# Stylophone.net
KiCad netlist of a schematic drawn in Altium Designer
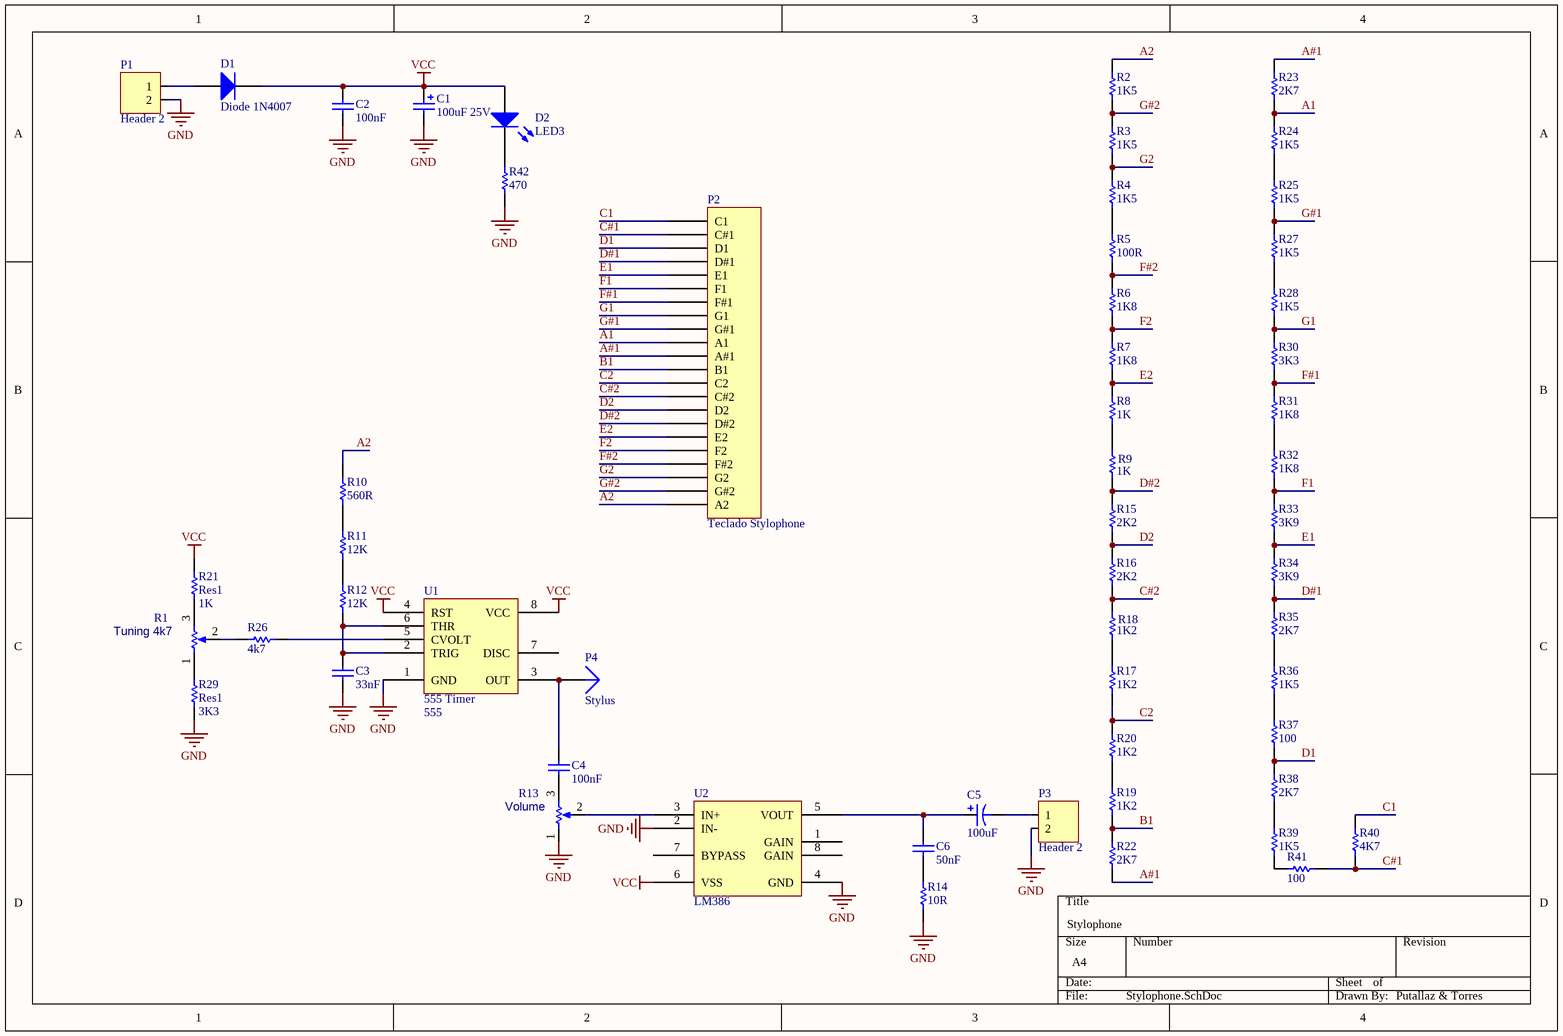
[diagram p0: Stylophone.SchDoc]

(export (version "E")
  (design (tool "Eeschema 10.0.6"))
  (components
    (comp (ref "C1")
      (value "100uF 25V")
      (footprint "CAP SMD 100uF 25V")
      (description "Polarized Capacitor (Radial)")
      (fields (field (name "PUBLISHER") "Altium Limited"))
      (libsource (lib "SchLibPutallaz") (part "Cap Pol1"))
    )
    (comp (ref "C2")
      (value "100nF")
      (footprint "0805 res-cap")
      (description "Capacitor")
      (fields (field (name "PUBLISHER") "Altium Limited"))
      (libsource (lib "SchLibPutallaz") (part "Cap"))
    )
    (comp (ref "C3")
      (value "33nF")
      (footprint "0805 res-cap")
      (description "Capacitor")
      (fields (field (name "PUBLISHER") "Altium Limited"))
      (libsource (lib "SchLibPutallaz") (part "Cap"))
    )
    (comp (ref "C4")
      (value "100nF")
      (footprint "0805 res-cap")
      (description "Capacitor")
      (fields (field (name "PUBLISHER") "Altium Limited"))
      (libsource (lib "SchLibPutallaz") (part "Cap"))
    )
    (comp (ref "C5")
      (value "100uF")
      (footprint "CAP SMD 100uF 25V")
      (description "Polarized Capacitor (Axial)")
      (fields (field (name "PUBLISHER") "Altium Limited"))
      (libsource (lib "SchLibPutallaz") (part "Cap Pol D16mm"))
    )
    (comp (ref "C6")
      (value "50nF")
      (footprint "0805 res-cap")
      (description "Capacitor")
      (fields (field (name "PUBLISHER") "Altium Limited"))
      (libsource (lib "SchLibPutallaz") (part "Cap"))
    )
    (comp (ref "D1")
      (value "Diode 1N4007")
      (footprint "DO214AC")
      (description "1 Amp General Purpose Rectifier")
      (fields (field (name "PUBLISHER") "Altium Limited"))
      (libsource (lib "SchLibPutallaz") (part "Diode 1N4007"))
    )
    (comp (ref "D2")
      (value "LED3")
      (footprint "1206 LED")
      (description "Typical BLUE SiC LED")
      (fields (field (name "PUBLISHER") "Altium Limited"))
      (libsource (lib "SchLibPutallaz") (part "LED3"))
    )
    (comp (ref "P1")
      (value "Header 2")
      (footprint "HDR1X2")
      (description "Header, 2-Pin")
      (fields (field (name "PUBLISHER") "Altium Limited"))
      (libsource (lib "SchLibPutallaz") (part "Header 2"))
    )
    (comp (ref "P2")
      (value "Teclado Stylophone")
      (footprint "Teclado Stylophone")
      (libsource (lib "SchLibPutallaz") (part "Teclado Stylophone"))
    )
    (comp (ref "P3")
      (value "Header 2")
      (footprint "HDR1X2")
      (description "Header, 2-Pin")
      (fields (field (name "PUBLISHER") "Altium Limited"))
      (libsource (lib "") (part "Header 2_1"))
    )
    (comp (ref "P4")
      (value "Stylus")
      (footprint "PIN1")
      (description "Plug")
      (fields (field (name "PUBLISHER") "Altium Limited"))
      (libsource (lib "Miscellaneous Connectors") (part "Plug"))
    )
    (comp (ref "R1")
      (value "Tuning 4k7")
      (footprint "TRIMMING POTENTIOMETER")
      (description "4K7")
      (libsource (lib "Simulation Generic Components") (part "Potentiometer"))
    )
    (comp (ref "R2")
      (value "1K5")
      (footprint "0805 res")
      (description "Resistor")
      (fields (field (name "PUBLISHER") "Altium Limited"))
      (libsource (lib "SchLibPutallaz") (part "Res1"))
    )
    (comp (ref "R3")
      (value "1K5")
      (footprint "0805 res")
      (description "Resistor")
      (fields (field (name "PUBLISHER") "Altium Limited"))
      (libsource (lib "SchLibPutallaz") (part "Res1"))
    )
    (comp (ref "R4")
      (value "1K5")
      (footprint "0805 res")
      (description "Resistor")
      (fields (field (name "PUBLISHER") "Altium Limited"))
      (libsource (lib "SchLibPutallaz") (part "Res1"))
    )
    (comp (ref "R5")
      (value "100R")
      (footprint "0805 res")
      (description "Resistor")
      (fields (field (name "PUBLISHER") "Altium Limited"))
      (libsource (lib "SchLibPutallaz") (part "Res1"))
    )
    (comp (ref "R6")
      (value "1K8")
      (footprint "0805 res")
      (description "Resistor")
      (fields (field (name "PUBLISHER") "Altium Limited"))
      (libsource (lib "SchLibPutallaz") (part "Res1"))
    )
    (comp (ref "R7")
      (value "1K8")
      (footprint "0805 res")
      (description "Resistor")
      (fields (field (name "PUBLISHER") "Altium Limited"))
      (libsource (lib "SchLibPutallaz") (part "Res1"))
    )
    (comp (ref "R8")
      (value "1K")
      (footprint "0805 res")
      (description "Resistor")
      (fields (field (name "PUBLISHER") "Altium Limited"))
      (libsource (lib "SchLibPutallaz") (part "Res1"))
    )
    (comp (ref "R9")
      (value "1K")
      (footprint "0805 res")
      (description "Resistor")
      (fields (field (name "PUBLISHER") "Altium Limited"))
      (libsource (lib "SchLibPutallaz") (part "Res1"))
    )
    (comp (ref "R10")
      (value "560R")
      (footprint "0805 res")
      (description "Resistor")
      (fields (field (name "PUBLISHER") "Altium Limited"))
      (libsource (lib "SchLibPutallaz") (part "Res1"))
    )
    (comp (ref "R11")
      (value "12K")
      (footprint "0805 res")
      (description "Resistor")
      (fields (field (name "PUBLISHER") "Altium Limited"))
      (libsource (lib "SchLibPutallaz") (part "Res1"))
    )
    (comp (ref "R12")
      (value "12K")
      (footprint "0805 res")
      (description "Resistor")
      (fields (field (name "PUBLISHER") "Altium Limited"))
      (libsource (lib "SchLibPutallaz") (part "Res1"))
    )
    (comp (ref "R13")
      (value "Volume")
      (footprint "TRIMMING POTENTIOMETER")
      (description "4K7")
      (libsource (lib "Simulation Generic Components") (part "Potentiometer"))
    )
    (comp (ref "R14")
      (value "10R")
      (footprint "0805 res")
      (description "Resistor")
      (fields (field (name "PUBLISHER") "Altium Limited"))
      (libsource (lib "SchLibPutallaz") (part "Res1"))
    )
    (comp (ref "R15")
      (value "2K2")
      (footprint "0805 res")
      (description "Resistor")
      (fields (field (name "PUBLISHER") "Altium Limited"))
      (libsource (lib "SchLibPutallaz") (part "Res1"))
    )
    (comp (ref "R16")
      (value "2K2")
      (footprint "0805 res")
      (description "Resistor")
      (fields (field (name "PUBLISHER") "Altium Limited"))
      (libsource (lib "SchLibPutallaz") (part "Res1"))
    )
    (comp (ref "R17")
      (value "1K2")
      (footprint "0805 res")
      (description "Resistor")
      (fields (field (name "PUBLISHER") "Altium Limited"))
      (libsource (lib "SchLibPutallaz") (part "Res1"))
    )
    (comp (ref "R18")
      (value "1K2")
      (footprint "0805 res")
      (description "Resistor")
      (fields (field (name "PUBLISHER") "Altium Limited"))
      (libsource (lib "SchLibPutallaz") (part "Res1"))
    )
    (comp (ref "R19")
      (value "1K2")
      (footprint "0805 res")
      (description "Resistor")
      (fields (field (name "PUBLISHER") "Altium Limited"))
      (libsource (lib "SchLibPutallaz") (part "Res1"))
    )
    (comp (ref "R20")
      (value "1K2")
      (footprint "0805 res")
      (description "Resistor")
      (fields (field (name "PUBLISHER") "Altium Limited"))
      (libsource (lib "SchLibPutallaz") (part "Res1"))
    )
    (comp (ref "R21")
      (value "Res1")
      (footprint "0805 res")
      (description "Resistor")
      (fields (field (name "ALTIUM_VALUE") "1K") (field (name "PUBLISHER") "Altium Limited"))
      (libsource (lib "SchLibPutallaz") (part "Res1"))
    )
    (comp (ref "R22")
      (value "2K7")
      (footprint "0805 res")
      (description "Resistor")
      (fields (field (name "PUBLISHER") "Altium Limited"))
      (libsource (lib "SchLibPutallaz") (part "Res1"))
    )
    (comp (ref "R23")
      (value "2K7")
      (footprint "0805 res")
      (description "Resistor")
      (fields (field (name "PUBLISHER") "Altium Limited"))
      (libsource (lib "SchLibPutallaz") (part "Res1"))
    )
    (comp (ref "R24")
      (value "1K5")
      (footprint "0805 res")
      (description "Resistor")
      (fields (field (name "PUBLISHER") "Altium Limited"))
      (libsource (lib "SchLibPutallaz") (part "Res1"))
    )
    (comp (ref "R25")
      (value "1K5")
      (footprint "0805 res")
      (description "Resistor")
      (fields (field (name "PUBLISHER") "Altium Limited"))
      (libsource (lib "SchLibPutallaz") (part "Res1"))
    )
    (comp (ref "R26")
      (value "4k7")
      (footprint "0805 res")
      (description "Resistor")
      (fields (field (name "PUBLISHER") "Altium Limited"))
      (libsource (lib "SchLibPutallaz") (part "Res1"))
    )
    (comp (ref "R27")
      (value "1K5")
      (footprint "0805 res")
      (description "Resistor")
      (fields (field (name "PUBLISHER") "Altium Limited"))
      (libsource (lib "SchLibPutallaz") (part "Res1"))
    )
    (comp (ref "R28")
      (value "1K5")
      (footprint "0805 res")
      (description "Resistor")
      (fields (field (name "PUBLISHER") "Altium Limited"))
      (libsource (lib "SchLibPutallaz") (part "Res1"))
    )
    (comp (ref "R29")
      (value "Res1")
      (footprint "0805 res")
      (description "Resistor")
      (fields (field (name "ALTIUM_VALUE") "3K3") (field (name "PUBLISHER") "Altium Limited"))
      (libsource (lib "SchLibPutallaz") (part "Res1"))
    )
    (comp (ref "R30")
      (value "3K3")
      (footprint "0805 res")
      (description "Resistor")
      (fields (field (name "PUBLISHER") "Altium Limited"))
      (libsource (lib "SchLibPutallaz") (part "Res1"))
    )
    (comp (ref "R31")
      (value "1K8")
      (footprint "0805 res")
      (description "Resistor")
      (fields (field (name "PUBLISHER") "Altium Limited"))
      (libsource (lib "SchLibPutallaz") (part "Res1"))
    )
    (comp (ref "R32")
      (value "1K8")
      (footprint "0805 res")
      (description "Resistor")
      (fields (field (name "PUBLISHER") "Altium Limited"))
      (libsource (lib "SchLibPutallaz") (part "Res1"))
    )
    (comp (ref "R33")
      (value "3K9")
      (footprint "0805 res")
      (description "Resistor")
      (fields (field (name "PUBLISHER") "Altium Limited"))
      (libsource (lib "SchLibPutallaz") (part "Res1"))
    )
    (comp (ref "R34")
      (value "3K9")
      (footprint "0805 res")
      (description "Resistor")
      (fields (field (name "PUBLISHER") "Altium Limited"))
      (libsource (lib "SchLibPutallaz") (part "Res1"))
    )
    (comp (ref "R35")
      (value "2K7")
      (footprint "0805 res")
      (description "Resistor")
      (fields (field (name "PUBLISHER") "Altium Limited"))
      (libsource (lib "SchLibPutallaz") (part "Res1"))
    )
    (comp (ref "R36")
      (value "1K5")
      (footprint "0805 res")
      (description "Resistor")
      (fields (field (name "PUBLISHER") "Altium Limited"))
      (libsource (lib "SchLibPutallaz") (part "Res1"))
    )
    (comp (ref "R37")
      (value "100")
      (footprint "0805 res")
      (description "Resistor")
      (fields (field (name "PUBLISHER") "Altium Limited"))
      (libsource (lib "SchLibPutallaz") (part "Res1"))
    )
    (comp (ref "R38")
      (value "2K7")
      (footprint "0805 res")
      (description "Resistor")
      (fields (field (name "PUBLISHER") "Altium Limited"))
      (libsource (lib "SchLibPutallaz") (part "Res1"))
    )
    (comp (ref "R39")
      (value "1K5")
      (footprint "0805 res")
      (description "Resistor")
      (fields (field (name "PUBLISHER") "Altium Limited"))
      (libsource (lib "SchLibPutallaz") (part "Res1"))
    )
    (comp (ref "R40")
      (value "4K7")
      (footprint "0805 res")
      (description "Resistor")
      (fields (field (name "PUBLISHER") "Altium Limited"))
      (libsource (lib "SchLibPutallaz") (part "Res1"))
    )
    (comp (ref "R41")
      (value "100")
      (footprint "0805 res")
      (description "Resistor")
      (fields (field (name "PUBLISHER") "Altium Limited"))
      (libsource (lib "SchLibPutallaz") (part "Res1"))
    )
    (comp (ref "R42")
      (value "470")
      (footprint "0805 res")
      (description "Resistor")
      (fields (field (name "PUBLISHER") "Altium Limited"))
      (libsource (lib "SchLibPutallaz") (part "Res1"))
    )
    (comp (ref "U1") (value "555") (footprint "SOIC-8") (libsource (lib "SchLibPutallaz") (part "555")))
    (comp (ref "U2") (value "LM386") (footprint "SOIC-8") (libsource (lib "SchLibPutallaz") (part "LM386")))
  )
  (nets
    (net (code "1") (name "/A#1") (class "Default")
      (node (ref "P2") (pin "A#1") (pinfunction "A#1_A#1") (pintype "passive"))
      (node (ref "R22") (pin "1") (pinfunction "1_1") (pintype "passive"))
      (node (ref "R23") (pin "2") (pinfunction "2_2") (pintype "passive"))
    )
    (net (code "2") (name "/A1") (class "Default")
      (node (ref "P2") (pin "A1") (pinfunction "A1_A1") (pintype "passive"))
      (node (ref "R23") (pin "1") (pinfunction "1_1") (pintype "passive"))
      (node (ref "R24") (pin "2") (pinfunction "2_2") (pintype "passive"))
    )
    (net (code "3") (name "/A2") (class "Default")
      (node (ref "P2") (pin "A2") (pinfunction "A2_A2") (pintype "passive"))
      (node (ref "R10") (pin "2") (pinfunction "2_2") (pintype "passive"))
      (node (ref "R2") (pin "2") (pinfunction "2_2") (pintype "passive"))
    )
    (net (code "4") (name "/B1") (class "Default")
      (node (ref "P2") (pin "B1") (pinfunction "B1_B1") (pintype "passive"))
      (node (ref "R19") (pin "2") (pinfunction "2_2") (pintype "passive"))
      (node (ref "R22") (pin "2") (pinfunction "2_2") (pintype "passive"))
    )
    (net (code "5") (name "/C#1") (class "Default")
      (node (ref "P2") (pin "C#1") (pinfunction "C#1_C#1") (pintype "passive"))
      (node (ref "R40") (pin "1") (pinfunction "1_1") (pintype "passive"))
      (node (ref "R41") (pin "1") (pinfunction "1_1") (pintype "passive"))
    )
    (net (code "6") (name "/C#2") (class "Default")
      (node (ref "P2") (pin "C#2") (pinfunction "C#2_C#2") (pintype "passive"))
      (node (ref "R16") (pin "1") (pinfunction "1_1") (pintype "passive"))
      (node (ref "R18") (pin "1") (pinfunction "1_1") (pintype "passive"))
    )
    (net (code "7") (name "/C1") (class "Default")
      (node (ref "P2") (pin "C1") (pinfunction "C1_C1") (pintype "passive"))
      (node (ref "R40") (pin "2") (pinfunction "2_2") (pintype "passive"))
    )
    (net (code "8") (name "/C2") (class "Default")
      (node (ref "P2") (pin "C2") (pinfunction "C2_C2") (pintype "passive"))
      (node (ref "R17") (pin "1") (pinfunction "1_1") (pintype "passive"))
      (node (ref "R20") (pin "1") (pinfunction "1_1") (pintype "passive"))
    )
    (net (code "9") (name "/D#1") (class "Default")
      (node (ref "P2") (pin "D#1") (pinfunction "D#1_D#1") (pintype "passive"))
      (node (ref "R34") (pin "1") (pinfunction "1_1") (pintype "passive"))
      (node (ref "R35") (pin "2") (pinfunction "2_2") (pintype "passive"))
    )
    (net (code "10") (name "/D#2") (class "Default")
      (node (ref "P2") (pin "D#2") (pinfunction "D#2_D#2") (pintype "passive"))
      (node (ref "R15") (pin "2") (pinfunction "2_2") (pintype "passive"))
      (node (ref "R9") (pin "1") (pinfunction "1_1") (pintype "passive"))
    )
    (net (code "11") (name "/D1") (class "Default")
      (node (ref "P2") (pin "D1") (pinfunction "D1_D1") (pintype "passive"))
      (node (ref "R37") (pin "1") (pinfunction "1_1") (pintype "passive"))
      (node (ref "R38") (pin "2") (pinfunction "2_2") (pintype "passive"))
    )
    (net (code "12") (name "/D2") (class "Default")
      (node (ref "P2") (pin "D2") (pinfunction "D2_D2") (pintype "passive"))
      (node (ref "R15") (pin "1") (pinfunction "1_1") (pintype "passive"))
      (node (ref "R16") (pin "2") (pinfunction "2_2") (pintype "passive"))
    )
    (net (code "13") (name "/E1") (class "Default")
      (node (ref "P2") (pin "E1") (pinfunction "E1_E1") (pintype "passive"))
      (node (ref "R33") (pin "1") (pinfunction "1_1") (pintype "passive"))
      (node (ref "R34") (pin "2") (pinfunction "2_2") (pintype "passive"))
    )
    (net (code "14") (name "/E2") (class "Default")
      (node (ref "P2") (pin "E2") (pinfunction "E2_E2") (pintype "passive"))
      (node (ref "R7") (pin "1") (pinfunction "1_1") (pintype "passive"))
      (node (ref "R8") (pin "1") (pinfunction "1_1") (pintype "passive"))
    )
    (net (code "15") (name "/F#1") (class "Default")
      (node (ref "P2") (pin "F#1") (pinfunction "F#1_F#1") (pintype "passive"))
      (node (ref "R30") (pin "1") (pinfunction "1_1") (pintype "passive"))
      (node (ref "R31") (pin "2") (pinfunction "2_2") (pintype "passive"))
    )
    (net (code "16") (name "/F#2") (class "Default")
      (node (ref "P2") (pin "F#2") (pinfunction "F#2_F#2") (pintype "passive"))
      (node (ref "R5") (pin "1") (pinfunction "1_1") (pintype "passive"))
      (node (ref "R6") (pin "2") (pinfunction "2_2") (pintype "passive"))
    )
    (net (code "17") (name "/F1") (class "Default")
      (node (ref "P2") (pin "F1") (pinfunction "F1_F1") (pintype "passive"))
      (node (ref "R32") (pin "1") (pinfunction "1_1") (pintype "passive"))
      (node (ref "R33") (pin "2") (pinfunction "2_2") (pintype "passive"))
    )
    (net (code "18") (name "/F2") (class "Default")
      (node (ref "P2") (pin "F2") (pinfunction "F2_F2") (pintype "passive"))
      (node (ref "R6") (pin "1") (pinfunction "1_1") (pintype "passive"))
      (node (ref "R7") (pin "2") (pinfunction "2_2") (pintype "passive"))
    )
    (net (code "19") (name "/G#1") (class "Default")
      (node (ref "P2") (pin "G#1") (pinfunction "G#1_G#1") (pintype "passive"))
      (node (ref "R25") (pin "1") (pinfunction "1_1") (pintype "passive"))
      (node (ref "R27") (pin "2") (pinfunction "2_2") (pintype "passive"))
    )
    (net (code "20") (name "/G#2") (class "Default")
      (node (ref "P2") (pin "G#2") (pinfunction "G#2_G#2") (pintype "passive"))
      (node (ref "R2") (pin "1") (pinfunction "1_1") (pintype "passive"))
      (node (ref "R3") (pin "2") (pinfunction "2_2") (pintype "passive"))
    )
    (net (code "21") (name "/G1") (class "Default")
      (node (ref "P2") (pin "G1") (pinfunction "G1_G1") (pintype "passive"))
      (node (ref "R28") (pin "1") (pinfunction "1_1") (pintype "passive"))
      (node (ref "R30") (pin "2") (pinfunction "2_2") (pintype "passive"))
    )
    (net (code "22") (name "/G2") (class "Default")
      (node (ref "P2") (pin "G2") (pinfunction "G2_G2") (pintype "passive"))
      (node (ref "R3") (pin "1") (pinfunction "1_1") (pintype "passive"))
      (node (ref "R4") (pin "2") (pinfunction "2_2") (pintype "passive"))
    )
    (net (code "23") (name "GND") (class "Default")
      (node (ref "C1") (pin "2") (pinfunction "2_2") (pintype "passive"))
      (node (ref "C2") (pin "1") (pinfunction "1_1") (pintype "passive"))
      (node (ref "C3") (pin "1") (pinfunction "1_1") (pintype "passive"))
      (node (ref "P1") (pin "2") (pinfunction "2_2") (pintype "passive"))
      (node (ref "P3") (pin "2") (pinfunction "2_2") (pintype "passive"))
      (node (ref "R13") (pin "1") (pinfunction "TOP_1") (pintype "passive"))
      (node (ref "R14") (pin "1") (pinfunction "1_1") (pintype "passive"))
      (node (ref "R29") (pin "1") (pinfunction "1_1") (pintype "passive"))
      (node (ref "R42") (pin "1") (pinfunction "1_1") (pintype "passive"))
      (node (ref "U1") (pin "1") (pinfunction "GND_1") (pintype "passive"))
      (node (ref "U2") (pin "2") (pinfunction "IN-_2") (pintype "passive"))
      (node (ref "U2") (pin "4") (pinfunction "GND_4") (pintype "passive"))
    )
    (net (code "24") (name "Net-(C5-Pad2)") (class "Default")
      (node (ref "C5") (pin "2") (pinfunction "2_2") (pintype "passive"))
      (node (ref "P3") (pin "1") (pinfunction "1_1") (pintype "passive"))
    )
    (net (code "25") (name "Net-(C6-Pad1)") (class "Default")
      (node (ref "C6") (pin "1") (pinfunction "1_1") (pintype "passive"))
      (node (ref "R14") (pin "2") (pinfunction "2_2") (pintype "passive"))
    )
    (net (code "26") (name "Net-(D1-A)") (class "Default")
      (node (ref "D1") (pin "1") (pinfunction "A_1") (pintype "passive"))
      (node (ref "P1") (pin "1") (pinfunction "1_1") (pintype "passive"))
    )
    (net (code "27") (name "Net-(D2-K)") (class "Default")
      (node (ref "D2") (pin "2") (pinfunction "K_2") (pintype "passive"))
      (node (ref "R42") (pin "2") (pinfunction "2_2") (pintype "passive"))
    )
    (net (code "28") (name "Net-(R1-BOT)") (class "Default")
      (node (ref "R1") (pin "3") (pinfunction "BOT_3") (pintype "passive"))
      (node (ref "R21") (pin "1") (pinfunction "1_1") (pintype "passive"))
    )
    (net (code "29") (name "Net-(R1-TAP)") (class "Default")
      (node (ref "R1") (pin "2") (pinfunction "TAP_2") (pintype "passive"))
      (node (ref "R26") (pin "1") (pinfunction "1_1") (pintype "passive"))
    )
    (net (code "30") (name "Net-(R1-TOP)") (class "Default")
      (node (ref "R1") (pin "1") (pinfunction "TOP_1") (pintype "passive"))
      (node (ref "R29") (pin "2") (pinfunction "2_2") (pintype "passive"))
    )
    (net (code "31") (name "Net-(R4-Pad1)") (class "Default")
      (node (ref "R4") (pin "1") (pinfunction "1_1") (pintype "passive"))
      (node (ref "R5") (pin "2") (pinfunction "2_2") (pintype "passive"))
    )
    (net (code "32") (name "Net-(R8-Pad2)") (class "Default")
      (node (ref "R8") (pin "2") (pinfunction "2_2") (pintype "passive"))
      (node (ref "R9") (pin "2") (pinfunction "2_2") (pintype "passive"))
    )
    (net (code "33") (name "Net-(R10-Pad1)") (class "Default")
      (node (ref "R10") (pin "1") (pinfunction "1_1") (pintype "passive"))
      (node (ref "R11") (pin "2") (pinfunction "2_2") (pintype "passive"))
    )
    (net (code "34") (name "Net-(R11-Pad1)") (class "Default")
      (node (ref "R11") (pin "1") (pinfunction "1_1") (pintype "passive"))
      (node (ref "R12") (pin "2") (pinfunction "2_2") (pintype "passive"))
    )
    (net (code "35") (name "Net-(R13-BOT)") (class "Default")
      (node (ref "C4") (pin "2") (pinfunction "2_2") (pintype "passive"))
      (node (ref "R13") (pin "3") (pinfunction "BOT_3") (pintype "passive"))
    )
    (net (code "36") (name "Net-(R13-TAP)") (class "Default")
      (node (ref "R13") (pin "2") (pinfunction "TAP_2") (pintype "passive"))
      (node (ref "U2") (pin "3") (pinfunction "IN+_3") (pintype "passive"))
    )
    (net (code "37") (name "Net-(R17-Pad2)") (class "Default")
      (node (ref "R17") (pin "2") (pinfunction "2_2") (pintype "passive"))
      (node (ref "R18") (pin "2") (pinfunction "2_2") (pintype "passive"))
    )
    (net (code "38") (name "Net-(R19-Pad1)") (class "Default")
      (node (ref "R19") (pin "1") (pinfunction "1_1") (pintype "passive"))
      (node (ref "R20") (pin "2") (pinfunction "2_2") (pintype "passive"))
    )
    (net (code "39") (name "Net-(R24-Pad1)") (class "Default")
      (node (ref "R24") (pin "1") (pinfunction "1_1") (pintype "passive"))
      (node (ref "R25") (pin "2") (pinfunction "2_2") (pintype "passive"))
    )
    (net (code "40") (name "Net-(R27-Pad1)") (class "Default")
      (node (ref "R27") (pin "1") (pinfunction "1_1") (pintype "passive"))
      (node (ref "R28") (pin "2") (pinfunction "2_2") (pintype "passive"))
    )
    (net (code "41") (name "Net-(R31-Pad1)") (class "Default")
      (node (ref "R31") (pin "1") (pinfunction "1_1") (pintype "passive"))
      (node (ref "R32") (pin "2") (pinfunction "2_2") (pintype "passive"))
    )
    (net (code "42") (name "Net-(R35-Pad1)") (class "Default")
      (node (ref "R35") (pin "1") (pinfunction "1_1") (pintype "passive"))
      (node (ref "R36") (pin "2") (pinfunction "2_2") (pintype "passive"))
    )
    (net (code "43") (name "Net-(R36-Pad1)") (class "Default")
      (node (ref "R36") (pin "1") (pinfunction "1_1") (pintype "passive"))
      (node (ref "R37") (pin "2") (pinfunction "2_2") (pintype "passive"))
    )
    (net (code "44") (name "Net-(R38-Pad1)") (class "Default")
      (node (ref "R38") (pin "1") (pinfunction "1_1") (pintype "passive"))
      (node (ref "R39") (pin "2") (pinfunction "2_2") (pintype "passive"))
    )
    (net (code "45") (name "Net-(R39-Pad1)") (class "Default")
      (node (ref "R39") (pin "1") (pinfunction "1_1") (pintype "passive"))
      (node (ref "R41") (pin "2") (pinfunction "2_2") (pintype "passive"))
    )
    (net (code "46") (name "Net-(U1-CVOLT)") (class "Default")
      (node (ref "R26") (pin "2") (pinfunction "2_2") (pintype "passive"))
      (node (ref "U1") (pin "5") (pinfunction "CVOLT_5") (pintype "passive"))
    )
    (net (code "47") (name "Net-(U1-OUT)") (class "Default")
      (node (ref "C4") (pin "1") (pinfunction "1_1") (pintype "passive"))
      (node (ref "P4") (pin "1") (pinfunction "1_1") (pintype "passive"))
      (node (ref "U1") (pin "3") (pinfunction "OUT_3") (pintype "passive"))
    )
    (net (code "48") (name "Net-(U1-THR)") (class "Default")
      (node (ref "C3") (pin "2") (pinfunction "2_2") (pintype "passive"))
      (node (ref "R12") (pin "1") (pinfunction "1_1") (pintype "passive"))
      (node (ref "U1") (pin "2") (pinfunction "TRIG_2") (pintype "passive"))
      (node (ref "U1") (pin "6") (pinfunction "THR_6") (pintype "passive"))
    )
    (net (code "49") (name "Net-(U2-VOUT)") (class "Default")
      (node (ref "C5") (pin "1") (pinfunction "1_1") (pintype "passive"))
      (node (ref "C6") (pin "2") (pinfunction "2_2") (pintype "passive"))
      (node (ref "U2") (pin "5") (pinfunction "VOUT_5") (pintype "passive"))
    )
    (net (code "50") (name "VCC") (class "Default")
      (node (ref "C1") (pin "1") (pinfunction "1_1") (pintype "passive"))
      (node (ref "C2") (pin "2") (pinfunction "2_2") (pintype "passive"))
      (node (ref "D1") (pin "2") (pinfunction "K_2") (pintype "passive"))
      (node (ref "D2") (pin "1") (pinfunction "A_1") (pintype "passive"))
      (node (ref "R21") (pin "2") (pinfunction "2_2") (pintype "passive"))
      (node (ref "U1") (pin "4") (pinfunction "RST_4") (pintype "passive"))
      (node (ref "U1") (pin "8") (pinfunction "VCC_8") (pintype "passive"))
      (node (ref "U2") (pin "6") (pinfunction "VSS_6") (pintype "passive"))
    )
    (net (code "51") (name "unconnected-(U1-DISC-Pad7)") (class "Default")
      (node (ref "U1") (pin "7") (pinfunction "DISC_7") (pintype "passive"))
    )
    (net (code "52") (name "unconnected-(U2-BYPASS-Pad7)") (class "Default")
      (node (ref "U2") (pin "7") (pinfunction "BYPASS_7") (pintype "passive"))
    )
    (net (code "53") (name "unconnected-(U2-GAIN-Pad1)") (class "Default")
      (node (ref "U2") (pin "1") (pinfunction "GAIN_1") (pintype "passive"))
    )
    (net (code "54") (name "unconnected-(U2-GAIN-Pad8)") (class "Default")
      (node (ref "U2") (pin "8") (pinfunction "GAIN_8") (pintype "passive"))
    )
  )
)
